# SCH_Flight-Computer-V4_2024-07-29.net
KiCad netlist of a schematic drawn in EasyEDA
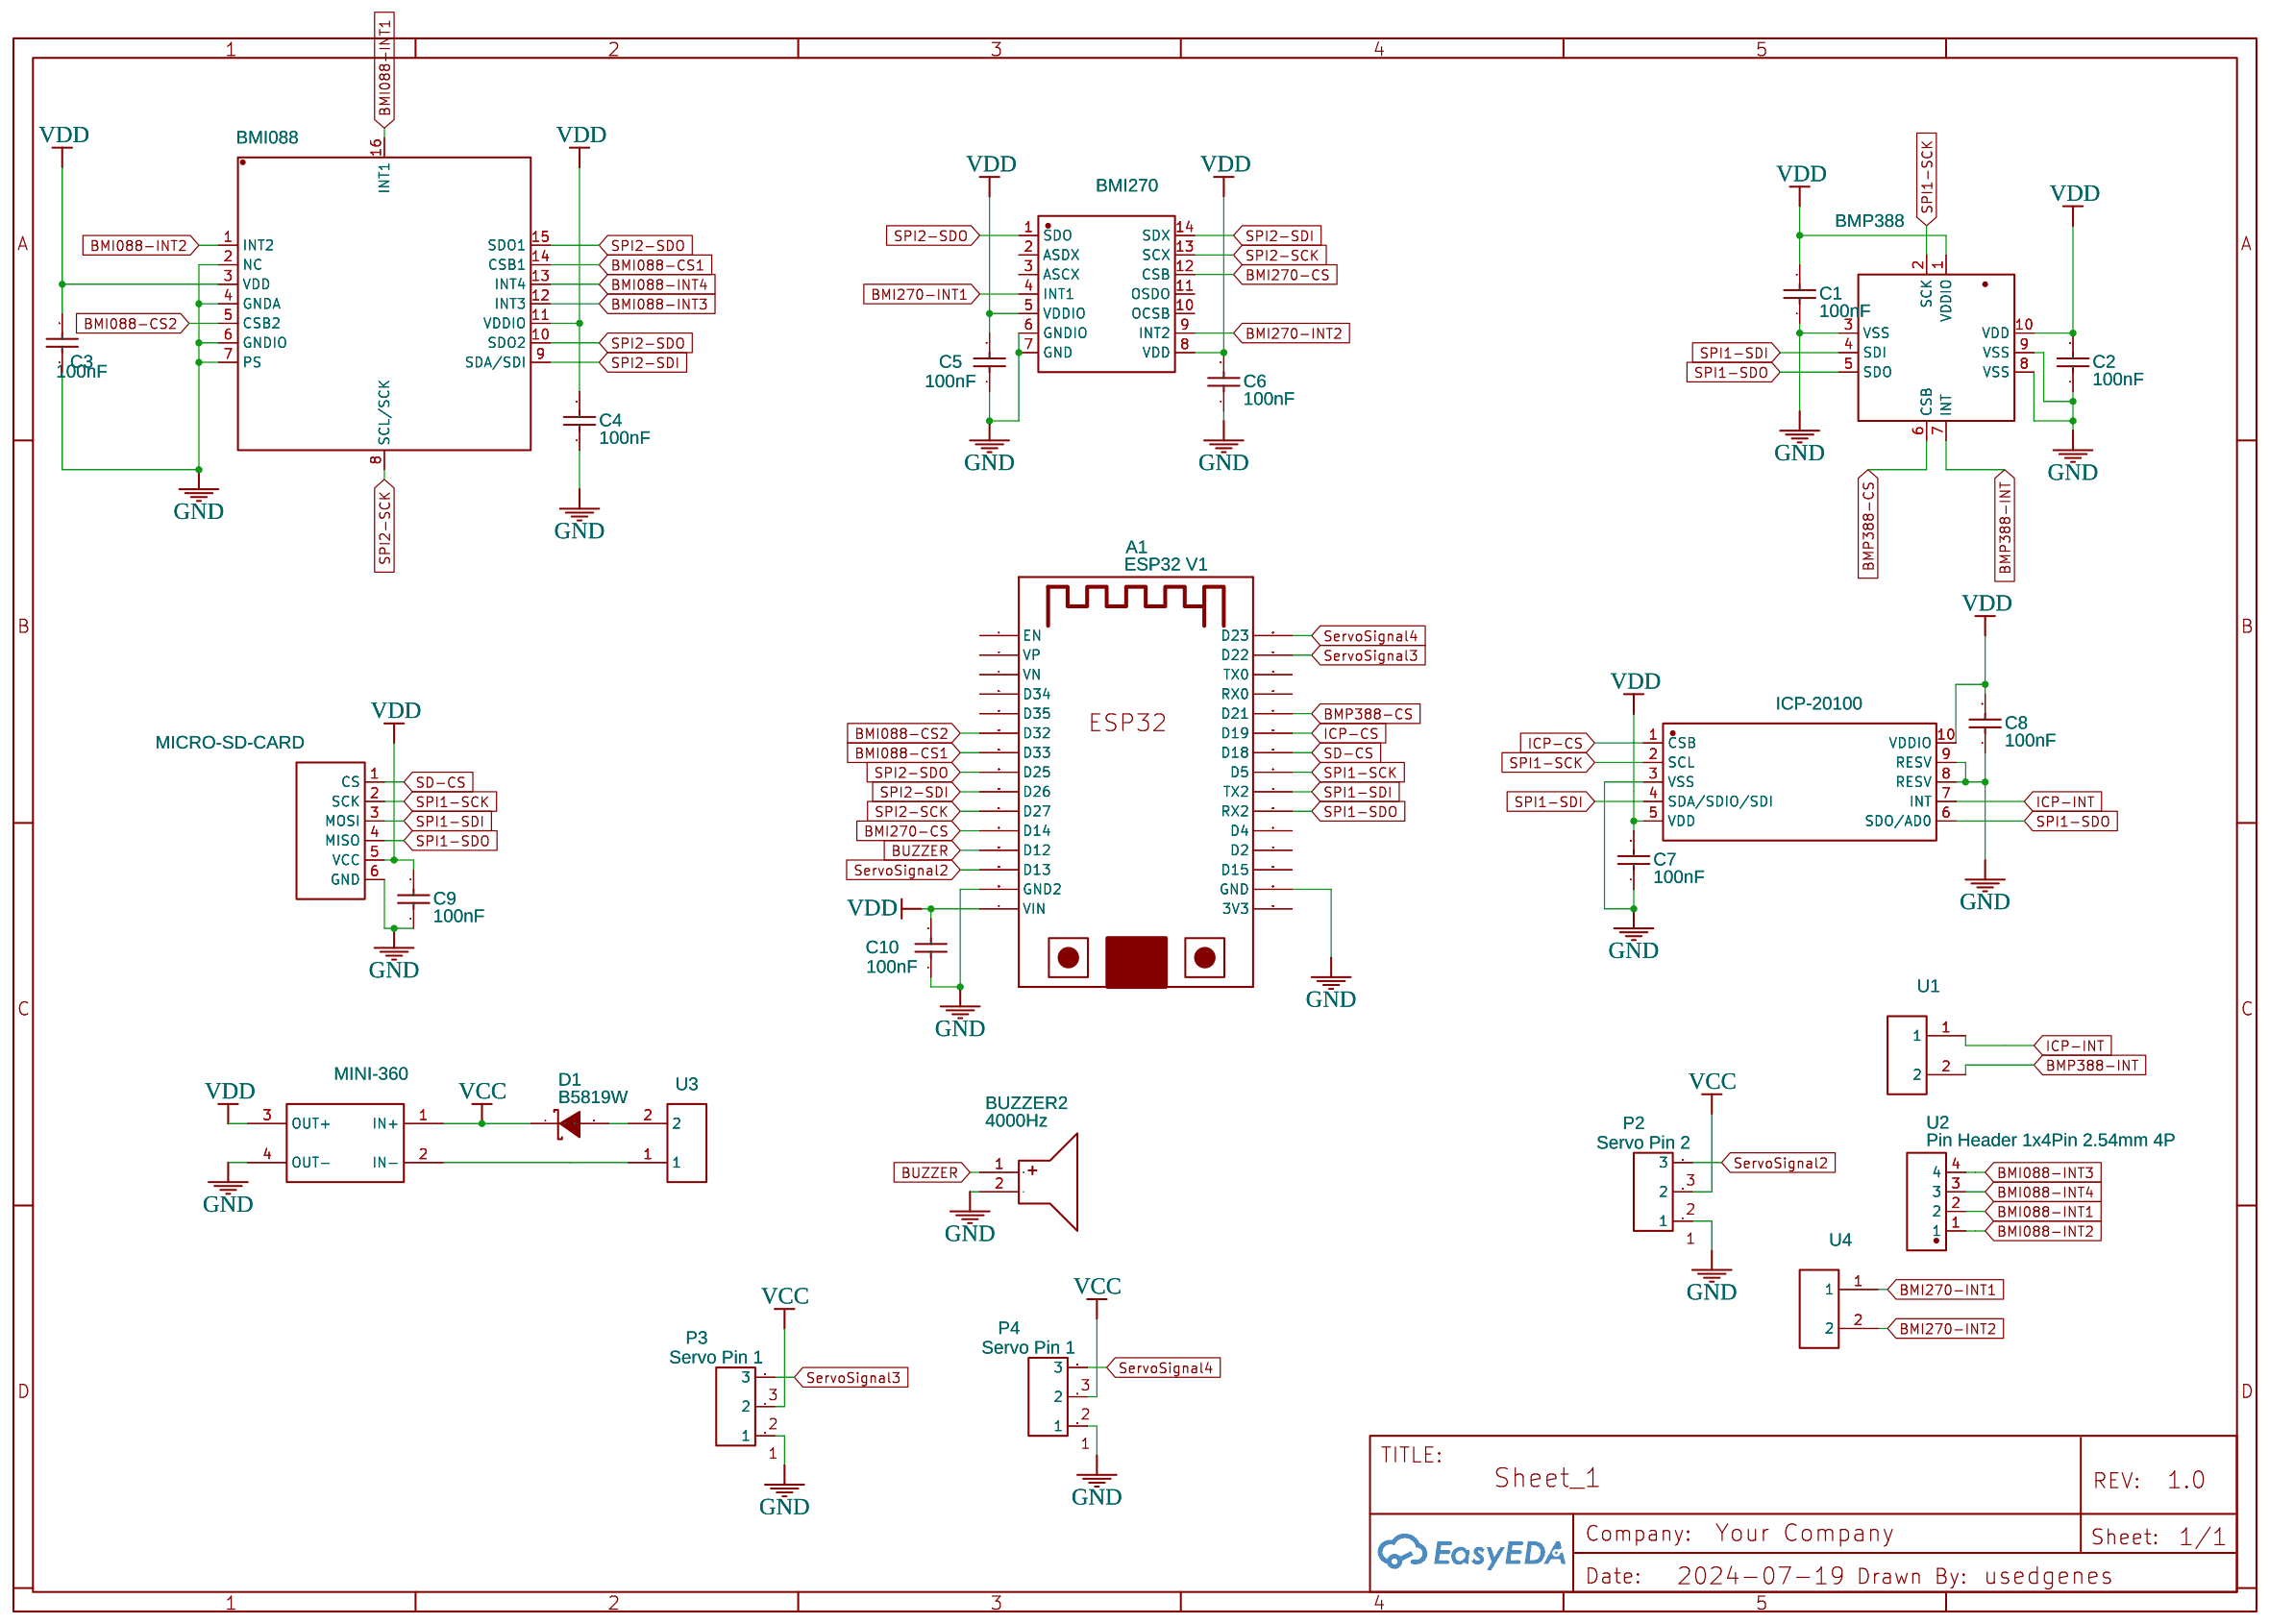
[diagram p0: schematic sheet]

(export (version "E")
  (design (tool "Eeschema 10.0.6"))
  (components
    (comp (ref "A1") (value "ESP32 V1") (libsource (lib "") (part "ESP32-DEVKIT-V1-30PIN")))
    (comp (ref "BMI088")
      (value "BMI088")
      (fields (field (name "Manufacturer") "Bosch(博世)"))
      (libsource (lib "") (part "BMI088"))
    )
    (comp (ref "BMI270")
      (value "BMI270")
      (fields (field (name "Manufacturer") "Bosch(博世)"))
      (libsource (lib "") (part "BMI270"))
    )
    (comp (ref "BMP388")
      (value "BMP388")
      (fields (field (name "Manufacturer") "Bosch(博世)"))
      (libsource (lib "") (part "BMP388"))
    )
    (comp (ref "BUZZER2")
      (value "4000Hz")
      (fields
        (field (name "Manufacturer Part") "SKY-1475-0540-45P7.6")
        (field (name "Manufacturer") "S&S(海旭)")
      )
      (libsource (lib "") (part "SKY-1475-0540-45P7.6"))
    )
    (comp (ref "C1")
      (value "100nF")
      (fields
        (field (name "Manufacturer Part") "CL05B104KO5NNNC")
        (field (name "Manufacturer") "SAMSUNG(三星)")
      )
      (libsource (lib "") (part "CL05B104KO5NNNC"))
    )
    (comp (ref "C2")
      (value "100nF")
      (fields
        (field (name "Manufacturer Part") "CL05B104KO5NNNC")
        (field (name "Manufacturer") "SAMSUNG(三星)")
      )
      (libsource (lib "") (part "CL05B104KO5NNNC"))
    )
    (comp (ref "C3")
      (value "100nF")
      (fields
        (field (name "Manufacturer Part") "CL05B104KO5NNNC")
        (field (name "Manufacturer") "SAMSUNG(三星)")
      )
      (libsource (lib "") (part "CL05B104KO5NNNC"))
    )
    (comp (ref "C4")
      (value "100nF")
      (fields
        (field (name "Manufacturer Part") "CL05B104KO5NNNC")
        (field (name "Manufacturer") "SAMSUNG(三星)")
      )
      (libsource (lib "") (part "CL05B104KO5NNNC"))
    )
    (comp (ref "C5")
      (value "100nF")
      (fields
        (field (name "Manufacturer Part") "CL05B104KO5NNNC")
        (field (name "Manufacturer") "SAMSUNG(三星)")
      )
      (libsource (lib "") (part "CL05B104KO5NNNC"))
    )
    (comp (ref "C6")
      (value "100nF")
      (fields
        (field (name "Manufacturer Part") "CL05B104KO5NNNC")
        (field (name "Manufacturer") "SAMSUNG(三星)")
      )
      (libsource (lib "") (part "CL05B104KO5NNNC"))
    )
    (comp (ref "C7")
      (value "100nF")
      (fields
        (field (name "Manufacturer Part") "CL05B104KO5NNNC")
        (field (name "Manufacturer") "SAMSUNG(三星)")
      )
      (libsource (lib "") (part "CL05B104KO5NNNC"))
    )
    (comp (ref "C8")
      (value "100nF")
      (fields
        (field (name "Manufacturer Part") "CL05B104KO5NNNC")
        (field (name "Manufacturer") "SAMSUNG(三星)")
      )
      (libsource (lib "") (part "CL05B104KO5NNNC"))
    )
    (comp (ref "C9")
      (value "100nF")
      (fields
        (field (name "Manufacturer Part") "CL05B104KO5NNNC")
        (field (name "Manufacturer") "SAMSUNG(三星)")
      )
      (libsource (lib "") (part "CL05B104KO5NNNC"))
    )
    (comp (ref "C10")
      (value "100nF")
      (fields
        (field (name "Manufacturer Part") "CL05B104KO5NNNC")
        (field (name "Manufacturer") "SAMSUNG(三星)")
      )
      (libsource (lib "") (part "CL05B104KO5NNNC"))
    )
    (comp (ref "D1")
      (value "B5819W")
      (fields (field (name "Manufacturer") "MDD(辰达半导体)"))
      (libsource (lib "") (part "B5819W"))
    )
    (comp (ref "ICP-20100")
      (value "ICP-20100")
      (fields (field (name "Manufacturer") "TDK"))
      (libsource (lib "") (part "ICP-20100"))
    )
    (comp (ref "MICRO-SD-CARD") (value "MicroSDCardAdapter") (libsource (lib "") (part "MicroSDCardAdapter")))
    (comp (ref "MINI-360") (value "MINI-360") (libsource (lib "") (part "MINI-360")))
    (comp (ref "P2")
      (value "Servo Pin 2")
      (fields
        (field (name "Manufacturer Part") "Female headerHDR1X8-2.54")
        (field (name "Manufacturer") "BOOMELE")
      )
      (libsource (lib "") (part "HEADER PAD 3X RMM COPY"))
    )
    (comp (ref "P3")
      (value "Servo Pin 1")
      (fields
        (field (name "Manufacturer Part") "Female headerHDR1X8-2.54")
        (field (name "Manufacturer") "BOOMELE")
      )
      (libsource (lib "") (part "HEADER PAD 3X RMM COPY"))
    )
    (comp (ref "P4")
      (value "Servo Pin 1")
      (fields
        (field (name "Manufacturer Part") "Female headerHDR1X8-2.54")
        (field (name "Manufacturer") "BOOMELE")
      )
      (libsource (lib "") (part "HEADER PAD 3X RMM COPY"))
    )
    (comp (ref "U1") (value "Power Pins") (libsource (lib "") (part "1X2")))
    (comp (ref "U2")
      (value "Pin Header 1x4Pin 2.54mm 4P")
      (libsource (lib "") (part "Pin Header 1x4Pin 2.54mm 4P"))
    )
    (comp (ref "U3") (value "Power Pins") (libsource (lib "") (part "1X2_1")))
    (comp (ref "U4") (value "Power Pins") (libsource (lib "") (part "1X2")))
  )
  (nets
    (net (code "1") (name "BMI088-CS1") (class "Default")
      (node (ref "A1") (pin "D33") (pinfunction "D33_D33") (pintype "unspecified"))
      (node (ref "BMI088") (pin "14") (pinfunction "CSB1_14") (pintype "unspecified"))
    )
    (net (code "2") (name "BMI088-CS2") (class "Default")
      (node (ref "A1") (pin "D32") (pinfunction "D32_D32") (pintype "unspecified"))
      (node (ref "BMI088") (pin "5") (pinfunction "CSB2_5") (pintype "unspecified"))
    )
    (net (code "3") (name "BMI088-INT1") (class "Default")
      (node (ref "BMI088") (pin "16") (pinfunction "INT1_16") (pintype "unspecified"))
      (node (ref "U2") (pin "2") (pinfunction "2_2") (pintype "unspecified"))
    )
    (net (code "4") (name "BMI088-INT2") (class "Default")
      (node (ref "BMI088") (pin "1") (pinfunction "INT2_1") (pintype "unspecified"))
      (node (ref "U2") (pin "1") (pinfunction "1_1") (pintype "unspecified"))
    )
    (net (code "5") (name "BMI088-INT3") (class "Default")
      (node (ref "BMI088") (pin "12") (pinfunction "INT3_12") (pintype "unspecified"))
      (node (ref "U2") (pin "4") (pinfunction "4_4") (pintype "unspecified"))
    )
    (net (code "6") (name "BMI088-INT4") (class "Default")
      (node (ref "BMI088") (pin "13") (pinfunction "INT4_13") (pintype "unspecified"))
      (node (ref "U2") (pin "3") (pinfunction "3_3") (pintype "unspecified"))
    )
    (net (code "7") (name "BMI270-CS") (class "Default")
      (node (ref "A1") (pin "D14") (pinfunction "D14_D14") (pintype "unspecified"))
      (node (ref "BMI270") (pin "12") (pinfunction "CSB_12") (pintype "unspecified"))
    )
    (net (code "8") (name "BMI270-INT1") (class "Default")
      (node (ref "BMI270") (pin "4") (pinfunction "INT1_4") (pintype "unspecified"))
      (node (ref "U4") (pin "1") (pinfunction "1_1") (pintype "unspecified"))
    )
    (net (code "9") (name "BMI270-INT2") (class "Default")
      (node (ref "BMI270") (pin "9") (pinfunction "INT2_9") (pintype "unspecified"))
      (node (ref "U4") (pin "2") (pinfunction "2_2") (pintype "unspecified"))
    )
    (net (code "10") (name "BMP388-CS") (class "Default")
      (node (ref "A1") (pin "D21") (pinfunction "D21_D21") (pintype "unspecified"))
      (node (ref "BMP388") (pin "6") (pinfunction "CSB_6") (pintype "unspecified"))
    )
    (net (code "11") (name "BMP388-INT") (class "Default")
      (node (ref "BMP388") (pin "7") (pinfunction "INT_7") (pintype "unspecified"))
      (node (ref "U1") (pin "2") (pinfunction "2_2") (pintype "unspecified"))
    )
    (net (code "12") (name "BUZZER") (class "Default")
      (node (ref "A1") (pin "D12") (pinfunction "D12_D12") (pintype "unspecified"))
      (node (ref "BUZZER2") (pin "1") (pinfunction "+_1") (pintype "unspecified"))
    )
    (net (code "13") (name "GND") (class "Default")
      (node (ref "A1") (pin "GND") (pinfunction "GND_GND") (pintype "unspecified"))
      (node (ref "A1") (pin "GND2") (pinfunction "GND2_GND2") (pintype "unspecified"))
      (node (ref "BMI088") (pin "2") (pinfunction "NC_2") (pintype "unspecified"))
      (node (ref "BMI088") (pin "4") (pinfunction "GNDA_4") (pintype "unspecified"))
      (node (ref "BMI088") (pin "6") (pinfunction "GNDIO_6") (pintype "unspecified"))
      (node (ref "BMI088") (pin "7") (pinfunction "PS_7") (pintype "unspecified"))
      (node (ref "BMI270") (pin "6") (pinfunction "GNDIO_6") (pintype "unspecified"))
      (node (ref "BMI270") (pin "7") (pinfunction "GND_7") (pintype "unspecified"))
      (node (ref "BMP388") (pin "3") (pinfunction "VSS_3") (pintype "unspecified"))
      (node (ref "BMP388") (pin "8") (pinfunction "VSS_8") (pintype "unspecified"))
      (node (ref "BMP388") (pin "9") (pinfunction "VSS_9") (pintype "unspecified"))
      (node (ref "BUZZER2") (pin "2") (pinfunction "-_2") (pintype "unspecified"))
      (node (ref "C1") (pin "1") (pinfunction "1_1") (pintype "input"))
      (node (ref "C10") (pin "1") (pinfunction "1_1") (pintype "input"))
      (node (ref "C2") (pin "1") (pinfunction "1_1") (pintype "input"))
      (node (ref "C3") (pin "1") (pinfunction "1_1") (pintype "input"))
      (node (ref "C4") (pin "1") (pinfunction "1_1") (pintype "input"))
      (node (ref "C5") (pin "1") (pinfunction "1_1") (pintype "input"))
      (node (ref "C6") (pin "1") (pinfunction "1_1") (pintype "input"))
      (node (ref "C7") (pin "1") (pinfunction "1_1") (pintype "input"))
      (node (ref "C8") (pin "1") (pinfunction "1_1") (pintype "input"))
      (node (ref "C9") (pin "1") (pinfunction "1_1") (pintype "input"))
      (node (ref "ICP-20100") (pin "3") (pinfunction "VSS_3") (pintype "unspecified"))
      (node (ref "ICP-20100") (pin "8") (pinfunction "RESV_8") (pintype "unspecified"))
      (node (ref "ICP-20100") (pin "9") (pinfunction "RESV_9") (pintype "unspecified"))
      (node (ref "MICRO-SD-CARD") (pin "6") (pinfunction "GND_6") (pintype "passive"))
      (node (ref "MINI-360") (pin "4") (pinfunction "OUT-_4") (pintype "unspecified"))
      (node (ref "P2") (pin "1") (pinfunction "1_1") (pintype "unspecified"))
      (node (ref "P3") (pin "1") (pinfunction "1_1") (pintype "unspecified"))
      (node (ref "P4") (pin "1") (pinfunction "1_1") (pintype "unspecified"))
    )
    (net (code "14") (name "ICP-CS") (class "Default")
      (node (ref "A1") (pin "D19") (pinfunction "D19_D19") (pintype "unspecified"))
      (node (ref "ICP-20100") (pin "1") (pinfunction "CSB_1") (pintype "unspecified"))
    )
    (net (code "15") (name "ICP-INT") (class "Default")
      (node (ref "ICP-20100") (pin "7") (pinfunction "INT_7") (pintype "unspecified"))
      (node (ref "U1") (pin "1") (pinfunction "1_1") (pintype "unspecified"))
    )
    (net (code "16") (name "Net-(D1-A)") (class "Default")
      (node (ref "D1") (pin "2") (pinfunction "A_2") (pintype "unspecified"))
      (node (ref "U3") (pin "2") (pinfunction "2_2") (pintype "unspecified"))
    )
    (net (code "17") (name "Net-(MINI-360-IN-)") (class "Default")
      (node (ref "MINI-360") (pin "2") (pinfunction "IN-_2") (pintype "unspecified"))
      (node (ref "U3") (pin "1") (pinfunction "1_1") (pintype "unspecified"))
    )
    (net (code "18") (name "SD-CS") (class "Default")
      (node (ref "A1") (pin "D18") (pinfunction "D18_D18") (pintype "unspecified"))
      (node (ref "MICRO-SD-CARD") (pin "1") (pinfunction "CS_1") (pintype "bidirectional"))
    )
    (net (code "19") (name "SPI1-SCK") (class "Default")
      (node (ref "A1") (pin "D5") (pinfunction "D5_D5") (pintype "unspecified"))
      (node (ref "BMP388") (pin "2") (pinfunction "SCK_2") (pintype "unspecified"))
      (node (ref "ICP-20100") (pin "2") (pinfunction "SCL_2") (pintype "unspecified"))
      (node (ref "MICRO-SD-CARD") (pin "2") (pinfunction "SCK_2") (pintype "bidirectional"))
    )
    (net (code "20") (name "SPI1-SDI") (class "Default")
      (node (ref "A1") (pin "TX2") (pinfunction "TX2_TX2") (pintype "unspecified"))
      (node (ref "BMP388") (pin "4") (pinfunction "SDI_4") (pintype "unspecified"))
      (node (ref "ICP-20100") (pin "4") (pinfunction "SDA/SDIO/SDI_4") (pintype "unspecified"))
      (node (ref "MICRO-SD-CARD") (pin "3") (pinfunction "MOSI_3") (pintype "passive"))
    )
    (net (code "21") (name "SPI1-SDO") (class "Default")
      (node (ref "A1") (pin "RX2") (pinfunction "RX2_RX2") (pintype "unspecified"))
      (node (ref "BMP388") (pin "5") (pinfunction "SDO_5") (pintype "unspecified"))
      (node (ref "ICP-20100") (pin "6") (pinfunction "SDO/AD0_6") (pintype "unspecified"))
      (node (ref "MICRO-SD-CARD") (pin "4") (pinfunction "MISO_4") (pintype "bidirectional"))
    )
    (net (code "22") (name "SPI2-SCK") (class "Default")
      (node (ref "A1") (pin "D27") (pinfunction "D27_D27") (pintype "unspecified"))
      (node (ref "BMI088") (pin "8") (pinfunction "SCL/SCK_8") (pintype "unspecified"))
      (node (ref "BMI270") (pin "13") (pinfunction "SCX_13") (pintype "unspecified"))
    )
    (net (code "23") (name "SPI2-SDI") (class "Default")
      (node (ref "A1") (pin "D26") (pinfunction "D26_D26") (pintype "unspecified"))
      (node (ref "BMI088") (pin "9") (pinfunction "SDA/SDI_9") (pintype "unspecified"))
      (node (ref "BMI270") (pin "14") (pinfunction "SDX_14") (pintype "unspecified"))
    )
    (net (code "24") (name "SPI2-SDO") (class "Default")
      (node (ref "A1") (pin "D25") (pinfunction "D25_D25") (pintype "unspecified"))
      (node (ref "BMI088") (pin "10") (pinfunction "SDO2_10") (pintype "unspecified"))
      (node (ref "BMI088") (pin "15") (pinfunction "SDO1_15") (pintype "unspecified"))
      (node (ref "BMI270") (pin "1") (pinfunction "SDO_1") (pintype "unspecified"))
    )
    (net (code "25") (name "ServoSignal2") (class "Default")
      (node (ref "A1") (pin "D13") (pinfunction "D13_D13") (pintype "unspecified"))
      (node (ref "P2") (pin "3") (pinfunction "3_3") (pintype "unspecified"))
    )
    (net (code "26") (name "ServoSignal3") (class "Default")
      (node (ref "A1") (pin "D22") (pinfunction "D22_D22") (pintype "unspecified"))
      (node (ref "P3") (pin "3") (pinfunction "3_3") (pintype "unspecified"))
    )
    (net (code "27") (name "ServoSignal4") (class "Default")
      (node (ref "A1") (pin "D23") (pinfunction "D23_D23") (pintype "unspecified"))
      (node (ref "P4") (pin "3") (pinfunction "3_3") (pintype "unspecified"))
    )
    (net (code "28") (name "VCC") (class "Default")
      (node (ref "D1") (pin "1") (pinfunction "K_1") (pintype "unspecified"))
      (node (ref "MINI-360") (pin "1") (pinfunction "IN+_1") (pintype "unspecified"))
      (node (ref "P2") (pin "2") (pinfunction "2_2") (pintype "unspecified"))
      (node (ref "P3") (pin "2") (pinfunction "2_2") (pintype "unspecified"))
      (node (ref "P4") (pin "2") (pinfunction "2_2") (pintype "unspecified"))
    )
    (net (code "29") (name "VDD") (class "Default")
      (node (ref "A1") (pin "VIN") (pinfunction "VIN_VIN") (pintype "unspecified"))
      (node (ref "BMI088") (pin "11") (pinfunction "VDDIO_11") (pintype "unspecified"))
      (node (ref "BMI088") (pin "3") (pinfunction "VDD_3") (pintype "unspecified"))
      (node (ref "BMI270") (pin "5") (pinfunction "VDDIO_5") (pintype "unspecified"))
      (node (ref "BMI270") (pin "8") (pinfunction "VDD_8") (pintype "unspecified"))
      (node (ref "BMP388") (pin "1") (pinfunction "VDDIO_1") (pintype "unspecified"))
      (node (ref "BMP388") (pin "10") (pinfunction "VDD_10") (pintype "unspecified"))
      (node (ref "C1") (pin "2") (pinfunction "2_2") (pintype "input"))
      (node (ref "C10") (pin "2") (pinfunction "2_2") (pintype "input"))
      (node (ref "C2") (pin "2") (pinfunction "2_2") (pintype "input"))
      (node (ref "C3") (pin "2") (pinfunction "2_2") (pintype "input"))
      (node (ref "C4") (pin "2") (pinfunction "2_2") (pintype "input"))
      (node (ref "C5") (pin "2") (pinfunction "2_2") (pintype "input"))
      (node (ref "C6") (pin "2") (pinfunction "2_2") (pintype "input"))
      (node (ref "C7") (pin "2") (pinfunction "2_2") (pintype "input"))
      (node (ref "C8") (pin "2") (pinfunction "2_2") (pintype "input"))
      (node (ref "C9") (pin "2") (pinfunction "2_2") (pintype "input"))
      (node (ref "ICP-20100") (pin "10") (pinfunction "VDDIO_10") (pintype "unspecified"))
      (node (ref "ICP-20100") (pin "5") (pinfunction "VDD_5") (pintype "unspecified"))
      (node (ref "MICRO-SD-CARD") (pin "5") (pinfunction "VCC_5") (pintype "passive"))
      (node (ref "MINI-360") (pin "3") (pinfunction "OUT+_3") (pintype "unspecified"))
    )
    (net (code "30") (name "unconnected-(A1-Pad3V3)") (class "Default")
      (node (ref "A1") (pin "3V3") (pinfunction "3V3_3V3") (pintype "unspecified"))
    )
    (net (code "31") (name "unconnected-(A1-PadD2)") (class "Default")
      (node (ref "A1") (pin "D2") (pinfunction "D2_D2") (pintype "unspecified"))
    )
    (net (code "32") (name "unconnected-(A1-PadD4)") (class "Default")
      (node (ref "A1") (pin "D4") (pinfunction "D4_D4") (pintype "unspecified"))
    )
    (net (code "33") (name "unconnected-(A1-PadD15)") (class "Default")
      (node (ref "A1") (pin "D15") (pinfunction "D15_D15") (pintype "unspecified"))
    )
    (net (code "34") (name "unconnected-(A1-PadD34)") (class "Default")
      (node (ref "A1") (pin "D34") (pinfunction "D34_D34") (pintype "unspecified"))
    )
    (net (code "35") (name "unconnected-(A1-PadD35)") (class "Default")
      (node (ref "A1") (pin "D35") (pinfunction "D35_D35") (pintype "unspecified"))
    )
    (net (code "36") (name "unconnected-(A1-PadEN)") (class "Default")
      (node (ref "A1") (pin "EN") (pinfunction "EN_EN") (pintype "unspecified"))
    )
    (net (code "37") (name "unconnected-(A1-PadRX0)") (class "Default")
      (node (ref "A1") (pin "RX0") (pinfunction "RX0_RX0") (pintype "unspecified"))
    )
    (net (code "38") (name "unconnected-(A1-PadTX0)") (class "Default")
      (node (ref "A1") (pin "TX0") (pinfunction "TX0_TX0") (pintype "unspecified"))
    )
    (net (code "39") (name "unconnected-(A1-PadVN)") (class "Default")
      (node (ref "A1") (pin "VN") (pinfunction "VN_VN") (pintype "unspecified"))
    )
    (net (code "40") (name "unconnected-(A1-PadVP)") (class "Default")
      (node (ref "A1") (pin "VP") (pinfunction "VP_VP") (pintype "unspecified"))
    )
    (net (code "41") (name "unconnected-(BMI270-ASCX-Pad3)") (class "Default")
      (node (ref "BMI270") (pin "3") (pinfunction "ASCX_3") (pintype "unspecified"))
    )
    (net (code "42") (name "unconnected-(BMI270-ASDX-Pad2)") (class "Default")
      (node (ref "BMI270") (pin "2") (pinfunction "ASDX_2") (pintype "unspecified"))
    )
    (net (code "43") (name "unconnected-(BMI270-OCSB-Pad10)") (class "Default")
      (node (ref "BMI270") (pin "10") (pinfunction "OCSB_10") (pintype "unspecified"))
    )
    (net (code "44") (name "unconnected-(BMI270-OSDO-Pad11)") (class "Default")
      (node (ref "BMI270") (pin "11") (pinfunction "OSDO_11") (pintype "unspecified"))
    )
  )
)
